# TSOC_NEOLED_R0_2.net
KiCad netlist of a schematic drawn in EAGLE
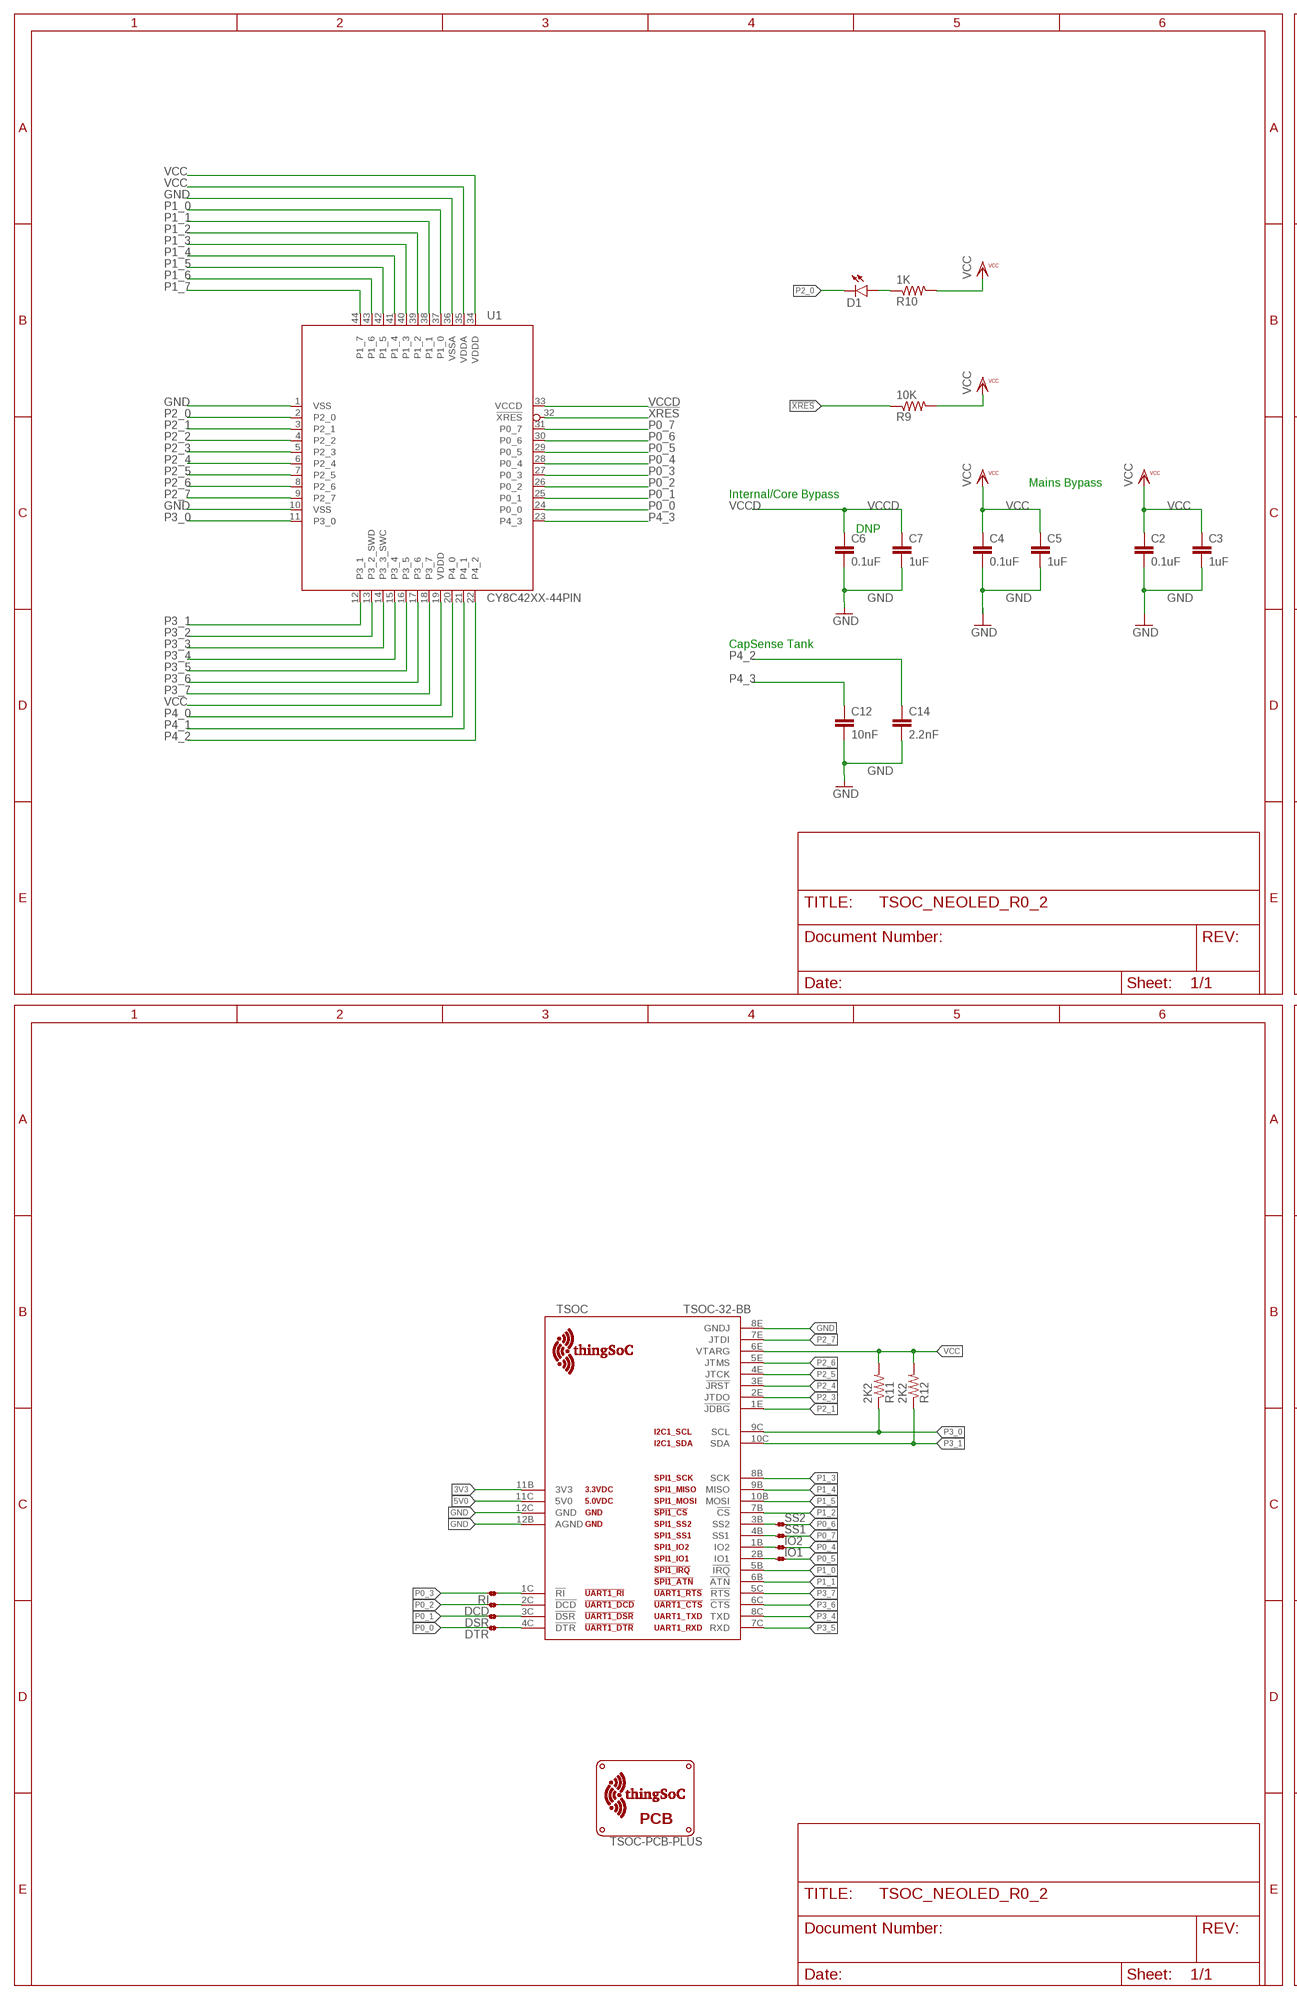
[diagram p0: schematic, sheet 1, part 1 of 2]
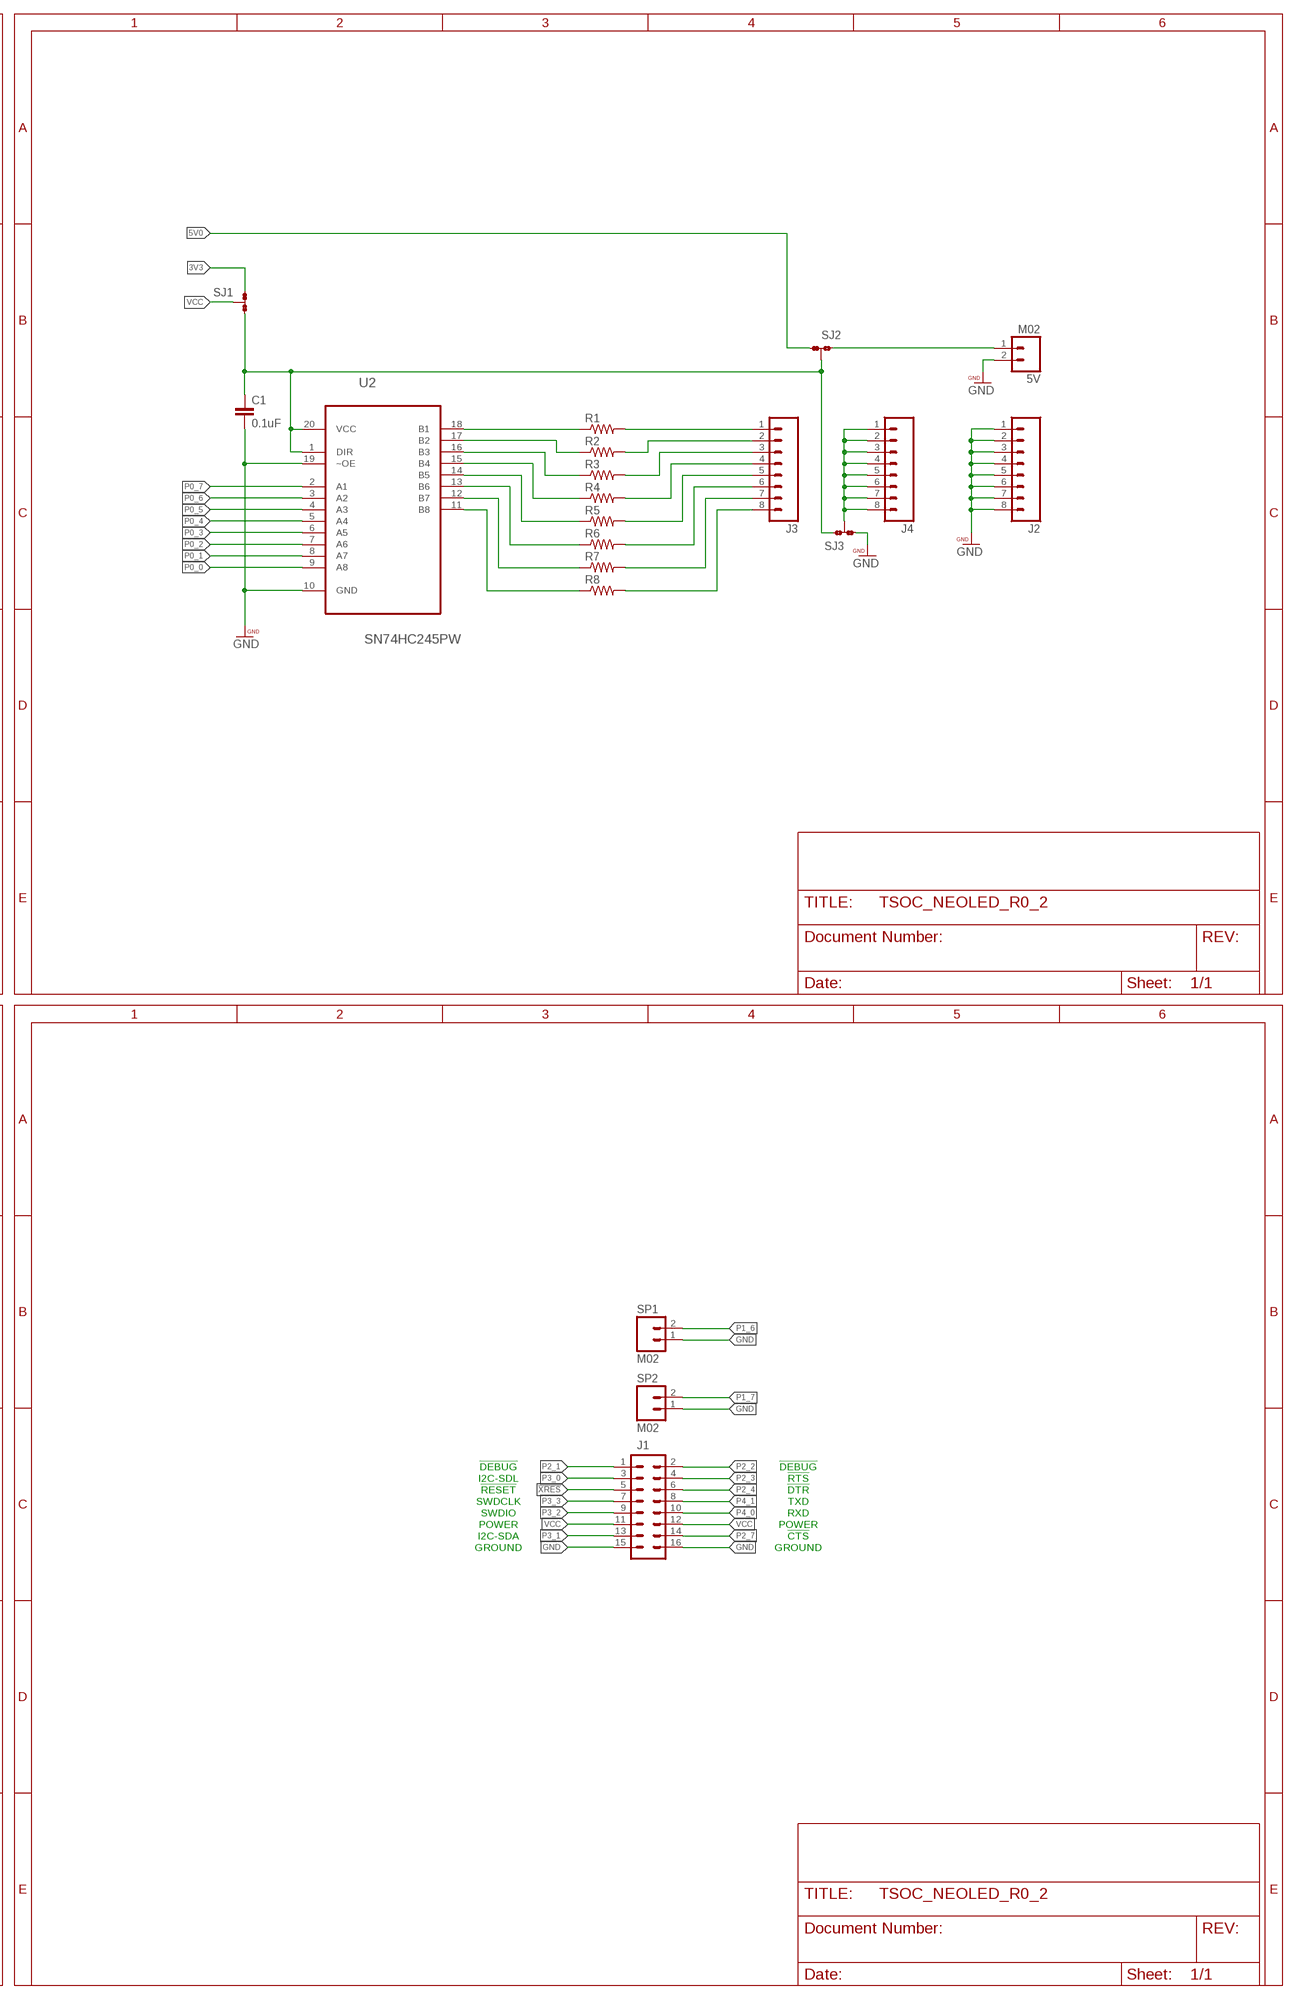
[diagram p1: schematic, sheet 1, part 2 of 2]

(export (version "E")
  (design (tool "Eeschema 10.0.6"))
  (components
    (comp (ref "5V")
      (value "M02")
      (footprint "eagle-import:1X02")
      (libsource (lib "eagle-import") (part "M02"))
    )
    (comp (ref "C1")
      (value "0.1uF")
      (footprint "eagle-import:0603-CAP")
      (libsource (lib "eagle-import") (part "CAP0603-CAP"))
    )
    (comp (ref "C2")
      (value "0.1uF")
      (footprint "eagle-import:0603-CAP")
      (libsource (lib "eagle-import") (part "CAP0603-CAP"))
    )
    (comp (ref "C3")
      (value "1uF")
      (footprint "eagle-import:0603-CAP")
      (libsource (lib "eagle-import") (part "CAP0603-CAP"))
    )
    (comp (ref "C4")
      (value "0.1uF")
      (footprint "eagle-import:0603-CAP")
      (libsource (lib "eagle-import") (part "CAP0603-CAP"))
    )
    (comp (ref "C5")
      (value "1uF")
      (footprint "eagle-import:0603-CAP")
      (libsource (lib "eagle-import") (part "CAP0603-CAP"))
    )
    (comp (ref "C6")
      (value "0.1uF")
      (footprint "eagle-import:0603-CAP")
      (libsource (lib "eagle-import") (part "CAP0603-CAP"))
    )
    (comp (ref "C7")
      (value "1uF")
      (footprint "eagle-import:0603-CAP")
      (libsource (lib "eagle-import") (part "CAP0603-CAP"))
    )
    (comp (ref "C12")
      (value "10nF")
      (footprint "eagle-import:0603-CAP")
      (libsource (lib "eagle-import") (part "CAP0603-CAP"))
    )
    (comp (ref "C14")
      (value "2.2nF")
      (footprint "eagle-import:0603-CAP")
      (libsource (lib "eagle-import") (part "CAP0603-CAP"))
    )
    (comp (ref "D1")
      (value "LED0603")
      (footprint "eagle-import:LED-0603")
      (libsource (lib "eagle-import") (part "LED0603"))
    )
    (comp (ref "DCD")
      (value "JMP-2-NO")
      (footprint "eagle-import:JMP-2-NO")
      (libsource (lib "eagle-import") (part "JMP-2-NO"))
    )
    (comp (ref "DSR")
      (value "JMP-2-NO")
      (footprint "eagle-import:JMP-2-NO")
      (libsource (lib "eagle-import") (part "JMP-2-NO"))
    )
    (comp (ref "DTR")
      (value "JMP-2-NO")
      (footprint "eagle-import:JMP-2-NO")
      (libsource (lib "eagle-import") (part "JMP-2-NO"))
    )
    (comp (ref "IO1")
      (value "JMP-2-NO")
      (footprint "eagle-import:JMP-2-NO")
      (libsource (lib "eagle-import") (part "JMP-2-NO"))
    )
    (comp (ref "IO2")
      (value "JMP-2-NO")
      (footprint "eagle-import:JMP-2-NO")
      (libsource (lib "eagle-import") (part "JMP-2-NO"))
    )
    (comp (ref "J1")
      (value "M08X2")
      (footprint "eagle-import:2X8")
      (libsource (lib "eagle-import") (part "M08X2"))
    )
    (comp (ref "J2")
      (value "M08")
      (footprint "eagle-import:1X08_ROUND")
      (libsource (lib "eagle-import") (part "M08"))
    )
    (comp (ref "J3")
      (value "M08")
      (footprint "eagle-import:1X08_ROUND")
      (libsource (lib "eagle-import") (part "M08"))
    )
    (comp (ref "J4")
      (value "M08")
      (footprint "eagle-import:1X08_ROUND")
      (libsource (lib "eagle-import") (part "M08"))
    )
    (comp (ref "R1")
      (value "RESISTOR0603-RES")
      (footprint "eagle-import:0603-RES")
      (libsource (lib "eagle-import") (part "RESISTOR0603-RES"))
    )
    (comp (ref "R2")
      (value "RESISTOR0603-RES")
      (footprint "eagle-import:0603-RES")
      (libsource (lib "eagle-import") (part "RESISTOR0603-RES"))
    )
    (comp (ref "R3")
      (value "RESISTOR0603-RES")
      (footprint "eagle-import:0603-RES")
      (libsource (lib "eagle-import") (part "RESISTOR0603-RES"))
    )
    (comp (ref "R4")
      (value "RESISTOR0603-RES")
      (footprint "eagle-import:0603-RES")
      (libsource (lib "eagle-import") (part "RESISTOR0603-RES"))
    )
    (comp (ref "R5")
      (value "RESISTOR0603-RES")
      (footprint "eagle-import:0603-RES")
      (libsource (lib "eagle-import") (part "RESISTOR0603-RES"))
    )
    (comp (ref "R6")
      (value "RESISTOR0603-RES")
      (footprint "eagle-import:0603-RES")
      (libsource (lib "eagle-import") (part "RESISTOR0603-RES"))
    )
    (comp (ref "R7")
      (value "RESISTOR0603-RES")
      (footprint "eagle-import:0603-RES")
      (libsource (lib "eagle-import") (part "RESISTOR0603-RES"))
    )
    (comp (ref "R8")
      (value "RESISTOR0603-RES")
      (footprint "eagle-import:0603-RES")
      (libsource (lib "eagle-import") (part "RESISTOR0603-RES"))
    )
    (comp (ref "R9")
      (value "10K")
      (footprint "eagle-import:0603-RES")
      (libsource (lib "eagle-import") (part "RESISTOR_SFE0603-RES"))
    )
    (comp (ref "R10")
      (value "1K")
      (footprint "eagle-import:0603-RES")
      (libsource (lib "eagle-import") (part "RESISTOR_SFE0603-RES"))
    )
    (comp (ref "R11")
      (value "2K2")
      (footprint "eagle-import:0603-RES")
      (libsource (lib "eagle-import") (part "RESISTOR_SFE0603-RES"))
    )
    (comp (ref "R12")
      (value "2K2")
      (footprint "eagle-import:0603-RES")
      (libsource (lib "eagle-import") (part "RESISTOR_SFE0603-RES"))
    )
    (comp (ref "RI")
      (value "JMP-2-NO")
      (footprint "eagle-import:JMP-2-NO")
      (libsource (lib "eagle-import") (part "JMP-2-NO"))
    )
    (comp (ref "SJ1")
      (value "JMP-3-1_2")
      (footprint "eagle-import:JMP-3-1_2")
      (libsource (lib "eagle-import") (part "JMP-3-1_2"))
    )
    (comp (ref "SJ2")
      (value "JMP-3-1_2")
      (footprint "eagle-import:JMP-3-1_2")
      (libsource (lib "eagle-import") (part "JMP-3-1_2"))
    )
    (comp (ref "SJ3")
      (value "JMP-3-1_2")
      (footprint "eagle-import:JMP-3-1_2")
      (libsource (lib "eagle-import") (part "JMP-3-1_2"))
    )
    (comp (ref "SP1")
      (value "M02")
      (footprint "eagle-import:1X02")
      (libsource (lib "eagle-import") (part "M02"))
    )
    (comp (ref "SP2")
      (value "M02")
      (footprint "eagle-import:1X02")
      (libsource (lib "eagle-import") (part "M02"))
    )
    (comp (ref "SS1")
      (value "JMP-2-NO")
      (footprint "eagle-import:JMP-2-NO")
      (libsource (lib "eagle-import") (part "JMP-2-NO"))
    )
    (comp (ref "SS2")
      (value "JMP-2-NO")
      (footprint "eagle-import:JMP-2-NO")
      (libsource (lib "eagle-import") (part "JMP-2-NO"))
    )
    (comp (ref "TSOC")
      (value "TSOC-32-BB")
      (footprint "eagle-import:TSOC-BB-S32")
      (libsource (lib "eagle-import") (part "TSOC-32-BB"))
    )
    (comp (ref "U$3")
      (value "TSOC-PCB-PLUS")
      (footprint "eagle-import:TSOC-BB-BRD-PLUS")
      (libsource (lib "eagle-import") (part "TSOC-PCB-PLUS"))
    )
    (comp (ref "U1")
      (value "CY8C42XX-44PIN")
      (footprint "eagle-import:TQFP-10X10-44")
      (libsource (lib "eagle-import") (part "CY8C42XX-44PIN"))
    )
    (comp (ref "U2")
      (value "SN74HC245PW")
      (footprint "eagle-import:SOP65P640X120-20N")
      (libsource (lib "eagle-import") (part "SN74HC245PW"))
    )
  )
  (nets
    (net (code "1") (name "/P4_2") (class "Default")
      (node (ref "C14") (pin "1") (pinfunction "1_1") (pintype "passive"))
      (node (ref "U1") (pin "22") (pinfunction "P4_2_22") (pintype "bidirectional"))
    )
    (net (code "2") (name "/P4_3") (class "Default")
      (node (ref "C12") (pin "1") (pinfunction "1_1") (pintype "passive"))
      (node (ref "U1") (pin "23") (pinfunction "P4_3_23") (pintype "bidirectional"))
    )
    (net (code "3") (name "/VCCD") (class "Default")
      (node (ref "C6") (pin "1") (pinfunction "1_1") (pintype "passive"))
      (node (ref "C7") (pin "1") (pinfunction "1_1") (pintype "passive"))
      (node (ref "U1") (pin "33") (pinfunction "VCCD_33") (pintype "bidirectional"))
    )
    (net (code "4") (name "/~{XRES}") (class "Default")
      (node (ref "J1") (pin "5") (pinfunction "5_5") (pintype "passive"))
      (node (ref "R9") (pin "1") (pinfunction "1_1") (pintype "passive"))
      (node (ref "U1") (pin "32") (pinfunction "~{XRES}_32") (pintype "bidirectional"))
    )
    (net (code "5") (name "3V3") (class "Default")
      (node (ref "SJ1") (pin "1") (pinfunction "1_1") (pintype "passive"))
      (node (ref "TSOC") (pin "11B") (pinfunction "3V3_11B") (pintype "bidirectional"))
    )
    (net (code "6") (name "5V0") (class "Default")
      (node (ref "SJ2") (pin "1") (pinfunction "1_1") (pintype "passive"))
      (node (ref "TSOC") (pin "11C") (pinfunction "5V0_11C") (pintype "bidirectional"))
    )
    (net (code "7") (name "GND") (class "Default")
      (node (ref "5V") (pin "2") (pinfunction "2_2") (pintype "passive"))
      (node (ref "C1") (pin "2") (pinfunction "2_2") (pintype "passive"))
      (node (ref "C12") (pin "2") (pinfunction "2_2") (pintype "passive"))
      (node (ref "C14") (pin "2") (pinfunction "2_2") (pintype "passive"))
      (node (ref "C2") (pin "2") (pinfunction "2_2") (pintype "passive"))
      (node (ref "C3") (pin "2") (pinfunction "2_2") (pintype "passive"))
      (node (ref "C4") (pin "2") (pinfunction "2_2") (pintype "passive"))
      (node (ref "C5") (pin "2") (pinfunction "2_2") (pintype "passive"))
      (node (ref "C6") (pin "2") (pinfunction "2_2") (pintype "passive"))
      (node (ref "C7") (pin "2") (pinfunction "2_2") (pintype "passive"))
      (node (ref "J1") (pin "15") (pinfunction "15_15") (pintype "passive"))
      (node (ref "J1") (pin "16") (pinfunction "16_16") (pintype "passive"))
      (node (ref "J2") (pin "1") (pinfunction "1_1") (pintype "passive"))
      (node (ref "J2") (pin "2") (pinfunction "2_2") (pintype "passive"))
      (node (ref "J2") (pin "3") (pinfunction "3_3") (pintype "passive"))
      (node (ref "J2") (pin "4") (pinfunction "4_4") (pintype "passive"))
      (node (ref "J2") (pin "5") (pinfunction "5_5") (pintype "passive"))
      (node (ref "J2") (pin "6") (pinfunction "6_6") (pintype "passive"))
      (node (ref "J2") (pin "7") (pinfunction "7_7") (pintype "passive"))
      (node (ref "J2") (pin "8") (pinfunction "8_8") (pintype "passive"))
      (node (ref "SJ3") (pin "1") (pinfunction "1_1") (pintype "passive"))
      (node (ref "SP1") (pin "1") (pinfunction "1_1") (pintype "passive"))
      (node (ref "SP2") (pin "1") (pinfunction "1_1") (pintype "passive"))
      (node (ref "TSOC") (pin "12B") (pinfunction "AGND_12B") (pintype "bidirectional"))
      (node (ref "TSOC") (pin "12C") (pinfunction "GND_12C") (pintype "bidirectional"))
      (node (ref "TSOC") (pin "8E") (pinfunction "GNDJ_8E") (pintype "bidirectional"))
      (node (ref "U1") (pin "1") (pinfunction "VSS_1") (pintype "bidirectional"))
      (node (ref "U1") (pin "10") (pinfunction "VSS_10") (pintype "bidirectional"))
      (node (ref "U1") (pin "36") (pinfunction "VSSA_36") (pintype "bidirectional"))
      (node (ref "U2") (pin "10") (pinfunction "GND_10") (pintype "input"))
      (node (ref "U2") (pin "19") (pinfunction "~{OE}_19") (pintype "input"))
    )
    (net (code "8") (name "Net-(5V-Pad1)") (class "Default")
      (node (ref "5V") (pin "1") (pinfunction "1_1") (pintype "passive"))
      (node (ref "SJ2") (pin "3") (pinfunction "3_3") (pintype "passive"))
    )
    (net (code "9") (name "Net-(D1-PadA)") (class "Default")
      (node (ref "D1") (pin "A") (pinfunction "A_A") (pintype "passive"))
      (node (ref "R10") (pin "1") (pinfunction "1_1") (pintype "passive"))
    )
    (net (code "10") (name "Net-(J3-Pad1)") (class "Default")
      (node (ref "J3") (pin "1") (pinfunction "1_1") (pintype "passive"))
      (node (ref "R1") (pin "2") (pinfunction "2_2") (pintype "passive"))
    )
    (net (code "11") (name "Net-(J3-Pad2)") (class "Default")
      (node (ref "J3") (pin "2") (pinfunction "2_2") (pintype "passive"))
      (node (ref "R2") (pin "2") (pinfunction "2_2") (pintype "passive"))
    )
    (net (code "12") (name "Net-(J3-Pad3)") (class "Default")
      (node (ref "J3") (pin "3") (pinfunction "3_3") (pintype "passive"))
      (node (ref "R3") (pin "2") (pinfunction "2_2") (pintype "passive"))
    )
    (net (code "13") (name "Net-(J3-Pad4)") (class "Default")
      (node (ref "J3") (pin "4") (pinfunction "4_4") (pintype "passive"))
      (node (ref "R4") (pin "2") (pinfunction "2_2") (pintype "passive"))
    )
    (net (code "14") (name "Net-(J3-Pad5)") (class "Default")
      (node (ref "J3") (pin "5") (pinfunction "5_5") (pintype "passive"))
      (node (ref "R5") (pin "2") (pinfunction "2_2") (pintype "passive"))
    )
    (net (code "15") (name "Net-(J3-Pad6)") (class "Default")
      (node (ref "J3") (pin "6") (pinfunction "6_6") (pintype "passive"))
      (node (ref "R6") (pin "2") (pinfunction "2_2") (pintype "passive"))
    )
    (net (code "16") (name "Net-(J3-Pad7)") (class "Default")
      (node (ref "J3") (pin "7") (pinfunction "7_7") (pintype "passive"))
      (node (ref "R7") (pin "2") (pinfunction "2_2") (pintype "passive"))
    )
    (net (code "17") (name "Net-(J3-Pad8)") (class "Default")
      (node (ref "J3") (pin "8") (pinfunction "8_8") (pintype "passive"))
      (node (ref "R8") (pin "2") (pinfunction "2_2") (pintype "passive"))
    )
    (net (code "18") (name "Net-(J4-Pad1)") (class "Default")
      (node (ref "J4") (pin "1") (pinfunction "1_1") (pintype "passive"))
      (node (ref "J4") (pin "2") (pinfunction "2_2") (pintype "passive"))
      (node (ref "J4") (pin "3") (pinfunction "3_3") (pintype "passive"))
      (node (ref "J4") (pin "4") (pinfunction "4_4") (pintype "passive"))
      (node (ref "J4") (pin "5") (pinfunction "5_5") (pintype "passive"))
      (node (ref "J4") (pin "6") (pinfunction "6_6") (pintype "passive"))
      (node (ref "J4") (pin "7") (pinfunction "7_7") (pintype "passive"))
      (node (ref "J4") (pin "8") (pinfunction "8_8") (pintype "passive"))
      (node (ref "SJ3") (pin "2") (pinfunction "2_2") (pintype "passive"))
    )
    (net (code "19") (name "Net-(TSOC-IO1)") (class "Default")
      (node (ref "IO1") (pin "1") (pinfunction "1_1") (pintype "passive"))
      (node (ref "TSOC") (pin "2B") (pinfunction "IO1_2B") (pintype "bidirectional"))
    )
    (net (code "20") (name "Net-(TSOC-IO2)") (class "Default")
      (node (ref "IO2") (pin "1") (pinfunction "1_1") (pintype "passive"))
      (node (ref "TSOC") (pin "1B") (pinfunction "IO2_1B") (pintype "bidirectional"))
    )
    (net (code "21") (name "Net-(TSOC-SS1)") (class "Default")
      (node (ref "SS1") (pin "1") (pinfunction "1_1") (pintype "passive"))
      (node (ref "TSOC") (pin "4B") (pinfunction "SS1_4B") (pintype "bidirectional"))
    )
    (net (code "22") (name "Net-(TSOC-SS2)") (class "Default")
      (node (ref "SS2") (pin "1") (pinfunction "1_1") (pintype "passive"))
      (node (ref "TSOC") (pin "3B") (pinfunction "SS2_3B") (pintype "bidirectional"))
    )
    (net (code "23") (name "Net-(TSOC-~{DCD})") (class "Default")
      (node (ref "DCD") (pin "1") (pinfunction "1_1") (pintype "passive"))
      (node (ref "TSOC") (pin "2C") (pinfunction "~{DCD}_2C") (pintype "bidirectional"))
    )
    (net (code "24") (name "Net-(TSOC-~{DSR})") (class "Default")
      (node (ref "DSR") (pin "1") (pinfunction "1_1") (pintype "passive"))
      (node (ref "TSOC") (pin "3C") (pinfunction "~{DSR}_3C") (pintype "bidirectional"))
    )
    (net (code "25") (name "Net-(TSOC-~{DTR})") (class "Default")
      (node (ref "DTR") (pin "1") (pinfunction "1_1") (pintype "passive"))
      (node (ref "TSOC") (pin "4C") (pinfunction "~{DTR}_4C") (pintype "bidirectional"))
    )
    (net (code "26") (name "Net-(TSOC-~{RI})") (class "Default")
      (node (ref "RI") (pin "1") (pinfunction "1_1") (pintype "passive"))
      (node (ref "TSOC") (pin "1C") (pinfunction "~{RI}_1C") (pintype "bidirectional"))
    )
    (net (code "27") (name "Net-(U2-B1)") (class "Default")
      (node (ref "R1") (pin "1") (pinfunction "1_1") (pintype "passive"))
      (node (ref "U2") (pin "18") (pinfunction "B1_18") (pintype "bidirectional"))
    )
    (net (code "28") (name "Net-(U2-B2)") (class "Default")
      (node (ref "R2") (pin "1") (pinfunction "1_1") (pintype "passive"))
      (node (ref "U2") (pin "17") (pinfunction "B2_17") (pintype "bidirectional"))
    )
    (net (code "29") (name "Net-(U2-B3)") (class "Default")
      (node (ref "R3") (pin "1") (pinfunction "1_1") (pintype "passive"))
      (node (ref "U2") (pin "16") (pinfunction "B3_16") (pintype "bidirectional"))
    )
    (net (code "30") (name "Net-(U2-B4)") (class "Default")
      (node (ref "R4") (pin "1") (pinfunction "1_1") (pintype "passive"))
      (node (ref "U2") (pin "15") (pinfunction "B4_15") (pintype "bidirectional"))
    )
    (net (code "31") (name "Net-(U2-B5)") (class "Default")
      (node (ref "R5") (pin "1") (pinfunction "1_1") (pintype "passive"))
      (node (ref "U2") (pin "14") (pinfunction "B5_14") (pintype "bidirectional"))
    )
    (net (code "32") (name "Net-(U2-B6)") (class "Default")
      (node (ref "R6") (pin "1") (pinfunction "1_1") (pintype "passive"))
      (node (ref "U2") (pin "13") (pinfunction "B6_13") (pintype "bidirectional"))
    )
    (net (code "33") (name "Net-(U2-B7)") (class "Default")
      (node (ref "R7") (pin "1") (pinfunction "1_1") (pintype "passive"))
      (node (ref "U2") (pin "12") (pinfunction "B7_12") (pintype "bidirectional"))
    )
    (net (code "34") (name "Net-(U2-B8)") (class "Default")
      (node (ref "R8") (pin "1") (pinfunction "1_1") (pintype "passive"))
      (node (ref "U2") (pin "11") (pinfunction "B8_11") (pintype "bidirectional"))
    )
    (net (code "35") (name "Net-(U2-DIR)") (class "Default")
      (node (ref "C1") (pin "1") (pinfunction "1_1") (pintype "passive"))
      (node (ref "SJ1") (pin "3") (pinfunction "3_3") (pintype "passive"))
      (node (ref "SJ2") (pin "2") (pinfunction "2_2") (pintype "passive"))
      (node (ref "SJ3") (pin "3") (pinfunction "3_3") (pintype "passive"))
      (node (ref "U2") (pin "1") (pinfunction "DIR_1") (pintype "input"))
      (node (ref "U2") (pin "20") (pinfunction "VCC_20") (pintype "power_in"))
    )
    (net (code "36") (name "P0_0") (class "Default")
      (node (ref "DTR") (pin "2") (pinfunction "2_2") (pintype "passive"))
      (node (ref "U1") (pin "24") (pinfunction "P0_0_24") (pintype "bidirectional"))
      (node (ref "U2") (pin "9") (pinfunction "A8_9") (pintype "bidirectional"))
    )
    (net (code "37") (name "P0_1") (class "Default")
      (node (ref "DSR") (pin "2") (pinfunction "2_2") (pintype "passive"))
      (node (ref "U1") (pin "25") (pinfunction "P0_1_25") (pintype "bidirectional"))
      (node (ref "U2") (pin "8") (pinfunction "A7_8") (pintype "bidirectional"))
    )
    (net (code "38") (name "P0_2") (class "Default")
      (node (ref "DCD") (pin "2") (pinfunction "2_2") (pintype "passive"))
      (node (ref "U1") (pin "26") (pinfunction "P0_2_26") (pintype "input"))
      (node (ref "U2") (pin "7") (pinfunction "A6_7") (pintype "bidirectional"))
    )
    (net (code "39") (name "P0_3") (class "Default")
      (node (ref "RI") (pin "2") (pinfunction "2_2") (pintype "passive"))
      (node (ref "U1") (pin "27") (pinfunction "P0_3_27") (pintype "bidirectional"))
      (node (ref "U2") (pin "6") (pinfunction "A5_6") (pintype "bidirectional"))
    )
    (net (code "40") (name "P0_4") (class "Default")
      (node (ref "IO2") (pin "2") (pinfunction "2_2") (pintype "passive"))
      (node (ref "U1") (pin "28") (pinfunction "P0_4_28") (pintype "bidirectional"))
      (node (ref "U2") (pin "5") (pinfunction "A4_5") (pintype "bidirectional"))
    )
    (net (code "41") (name "P0_5") (class "Default")
      (node (ref "IO1") (pin "2") (pinfunction "2_2") (pintype "passive"))
      (node (ref "U1") (pin "29") (pinfunction "P0_5_29") (pintype "bidirectional"))
      (node (ref "U2") (pin "4") (pinfunction "A3_4") (pintype "bidirectional"))
    )
    (net (code "42") (name "P0_6") (class "Default")
      (node (ref "SS2") (pin "2") (pinfunction "2_2") (pintype "passive"))
      (node (ref "U1") (pin "30") (pinfunction "P0_6_30") (pintype "power_in"))
      (node (ref "U2") (pin "3") (pinfunction "A2_3") (pintype "bidirectional"))
    )
    (net (code "43") (name "P0_7") (class "Default")
      (node (ref "SS1") (pin "2") (pinfunction "2_2") (pintype "passive"))
      (node (ref "U1") (pin "31") (pinfunction "P0_7_31") (pintype "bidirectional"))
      (node (ref "U2") (pin "2") (pinfunction "A1_2") (pintype "bidirectional"))
    )
    (net (code "44") (name "P1_0") (class "Default")
      (node (ref "TSOC") (pin "5B") (pinfunction "~{IRQ}_5B") (pintype "bidirectional"))
      (node (ref "U1") (pin "37") (pinfunction "P1_0_37") (pintype "bidirectional"))
    )
    (net (code "45") (name "P1_1") (class "Default")
      (node (ref "TSOC") (pin "6B") (pinfunction "~{ATN}_6B") (pintype "bidirectional"))
      (node (ref "U1") (pin "38") (pinfunction "P1_1_38") (pintype "bidirectional"))
    )
    (net (code "46") (name "P1_2") (class "Default")
      (node (ref "TSOC") (pin "7B") (pinfunction "~{CS}_7B") (pintype "bidirectional"))
      (node (ref "U1") (pin "39") (pinfunction "P1_2_39") (pintype "power_in"))
    )
    (net (code "47") (name "P1_3") (class "Default")
      (node (ref "TSOC") (pin "8B") (pinfunction "SCK_8B") (pintype "bidirectional"))
      (node (ref "U1") (pin "40") (pinfunction "P1_3_40") (pintype "bidirectional"))
    )
    (net (code "48") (name "P1_4") (class "Default")
      (node (ref "TSOC") (pin "9B") (pinfunction "MISO_9B") (pintype "bidirectional"))
      (node (ref "U1") (pin "41") (pinfunction "P1_4_41") (pintype "bidirectional"))
    )
    (net (code "49") (name "P1_5") (class "Default")
      (node (ref "TSOC") (pin "10B") (pinfunction "MOSI_10B") (pintype "bidirectional"))
      (node (ref "U1") (pin "42") (pinfunction "P1_5_42") (pintype "bidirectional"))
    )
    (net (code "50") (name "P1_6") (class "Default")
      (node (ref "SP1") (pin "2") (pinfunction "2_2") (pintype "passive"))
      (node (ref "U1") (pin "43") (pinfunction "P1_6_43") (pintype "bidirectional"))
    )
    (net (code "51") (name "P1_7") (class "Default")
      (node (ref "SP2") (pin "2") (pinfunction "2_2") (pintype "passive"))
      (node (ref "U1") (pin "44") (pinfunction "P1_7_44") (pintype "bidirectional"))
    )
    (net (code "52") (name "P2_0") (class "Default")
      (node (ref "D1") (pin "C") (pinfunction "C_C") (pintype "passive"))
      (node (ref "U1") (pin "2") (pinfunction "P2_0_2") (pintype "bidirectional"))
    )
    (net (code "53") (name "P2_1") (class "Default")
      (node (ref "J1") (pin "1") (pinfunction "1_1") (pintype "passive"))
      (node (ref "TSOC") (pin "1E") (pinfunction "~{JDBG}_1E") (pintype "bidirectional"))
      (node (ref "U1") (pin "3") (pinfunction "P2_1_3") (pintype "bidirectional"))
    )
    (net (code "54") (name "P2_2") (class "Default")
      (node (ref "J1") (pin "2") (pinfunction "2_2") (pintype "passive"))
      (node (ref "U1") (pin "4") (pinfunction "P2_2_4") (pintype "power_in"))
    )
    (net (code "55") (name "P2_3") (class "Default")
      (node (ref "J1") (pin "4") (pinfunction "4_4") (pintype "passive"))
      (node (ref "TSOC") (pin "2E") (pinfunction "JTDO_2E") (pintype "bidirectional"))
      (node (ref "U1") (pin "5") (pinfunction "P2_3_5") (pintype "bidirectional"))
    )
    (net (code "56") (name "P2_4") (class "Default")
      (node (ref "J1") (pin "6") (pinfunction "6_6") (pintype "passive"))
      (node (ref "TSOC") (pin "3E") (pinfunction "~{JRST}_3E") (pintype "bidirectional"))
      (node (ref "U1") (pin "6") (pinfunction "P2_4_6") (pintype "bidirectional"))
    )
    (net (code "57") (name "P2_5") (class "Default")
      (node (ref "TSOC") (pin "4E") (pinfunction "JTCK_4E") (pintype "bidirectional"))
      (node (ref "U1") (pin "7") (pinfunction "P2_5_7") (pintype "bidirectional"))
    )
    (net (code "58") (name "P2_6") (class "Default")
      (node (ref "TSOC") (pin "5E") (pinfunction "JTMS_5E") (pintype "bidirectional"))
      (node (ref "U1") (pin "8") (pinfunction "P2_6_8") (pintype "power_in"))
    )
    (net (code "59") (name "P2_7") (class "Default")
      (node (ref "J1") (pin "14") (pinfunction "14_14") (pintype "passive"))
      (node (ref "TSOC") (pin "7E") (pinfunction "JTDI_7E") (pintype "bidirectional"))
      (node (ref "U1") (pin "9") (pinfunction "P2_7_9") (pintype "bidirectional"))
    )
    (net (code "60") (name "P3_0") (class "Default")
      (node (ref "J1") (pin "3") (pinfunction "3_3") (pintype "passive"))
      (node (ref "R11") (pin "1") (pinfunction "1_1") (pintype "passive"))
      (node (ref "TSOC") (pin "9C") (pinfunction "SCL_9C") (pintype "bidirectional"))
      (node (ref "U1") (pin "11") (pinfunction "P3_0_11") (pintype "bidirectional"))
    )
    (net (code "61") (name "P3_1") (class "Default")
      (node (ref "J1") (pin "13") (pinfunction "13_13") (pintype "passive"))
      (node (ref "R12") (pin "1") (pinfunction "1_1") (pintype "passive"))
      (node (ref "TSOC") (pin "10C") (pinfunction "SDA_10C") (pintype "bidirectional"))
      (node (ref "U1") (pin "12") (pinfunction "P3_1_12") (pintype "bidirectional"))
    )
    (net (code "62") (name "P3_2") (class "Default")
      (node (ref "J1") (pin "9") (pinfunction "9_9") (pintype "passive"))
      (node (ref "U1") (pin "13") (pinfunction "P3_2_SWD_13") (pintype "bidirectional"))
    )
    (net (code "63") (name "P3_3") (class "Default")
      (node (ref "J1") (pin "7") (pinfunction "7_7") (pintype "passive"))
      (node (ref "U1") (pin "14") (pinfunction "P3_3_SWC_14") (pintype "bidirectional"))
    )
    (net (code "64") (name "P3_4") (class "Default")
      (node (ref "TSOC") (pin "8C") (pinfunction "TXD_8C") (pintype "bidirectional"))
      (node (ref "U1") (pin "15") (pinfunction "P3_4_15") (pintype "bidirectional"))
    )
    (net (code "65") (name "P3_5") (class "Default")
      (node (ref "TSOC") (pin "7C") (pinfunction "RXD_7C") (pintype "bidirectional"))
      (node (ref "U1") (pin "16") (pinfunction "P3_5_16") (pintype "bidirectional"))
    )
    (net (code "66") (name "P3_6") (class "Default")
      (node (ref "TSOC") (pin "6C") (pinfunction "~{CTS}_6C") (pintype "bidirectional"))
      (node (ref "U1") (pin "17") (pinfunction "P3_6_17") (pintype "power_in"))
    )
    (net (code "67") (name "P3_7") (class "Default")
      (node (ref "TSOC") (pin "5C") (pinfunction "~{RTS}_5C") (pintype "bidirectional"))
      (node (ref "U1") (pin "18") (pinfunction "P3_7_18") (pintype "bidirectional"))
    )
    (net (code "68") (name "P4_0") (class "Default")
      (node (ref "J1") (pin "10") (pinfunction "10_10") (pintype "passive"))
      (node (ref "U1") (pin "20") (pinfunction "P4_0_20") (pintype "bidirectional"))
    )
    (net (code "69") (name "P4_1") (class "Default")
      (node (ref "J1") (pin "8") (pinfunction "8_8") (pintype "passive"))
      (node (ref "U1") (pin "21") (pinfunction "P4_1_21") (pintype "bidirectional"))
    )
    (net (code "70") (name "VCC") (class "Default")
      (node (ref "C2") (pin "1") (pinfunction "1_1") (pintype "passive"))
      (node (ref "C3") (pin "1") (pinfunction "1_1") (pintype "passive"))
      (node (ref "C4") (pin "1") (pinfunction "1_1") (pintype "passive"))
      (node (ref "C5") (pin "1") (pinfunction "1_1") (pintype "passive"))
      (node (ref "J1") (pin "11") (pinfunction "11_11") (pintype "passive"))
      (node (ref "J1") (pin "12") (pinfunction "12_12") (pintype "passive"))
      (node (ref "R10") (pin "2") (pinfunction "2_2") (pintype "passive"))
      (node (ref "R11") (pin "2") (pinfunction "2_2") (pintype "passive"))
      (node (ref "R12") (pin "2") (pinfunction "2_2") (pintype "passive"))
      (node (ref "R9") (pin "2") (pinfunction "2_2") (pintype "passive"))
      (node (ref "SJ1") (pin "2") (pinfunction "2_2") (pintype "passive"))
      (node (ref "TSOC") (pin "6E") (pinfunction "VTARG_6E") (pintype "bidirectional"))
      (node (ref "U1") (pin "19") (pinfunction "VDDD_19") (pintype "bidirectional"))
      (node (ref "U1") (pin "34") (pinfunction "VDDD_34") (pintype "bidirectional"))
      (node (ref "U1") (pin "35") (pinfunction "VDDA_35") (pintype "bidirectional"))
    )
  )
)
